# Integrater.net
KiCad netlist of a schematic drawn in Altium Designer
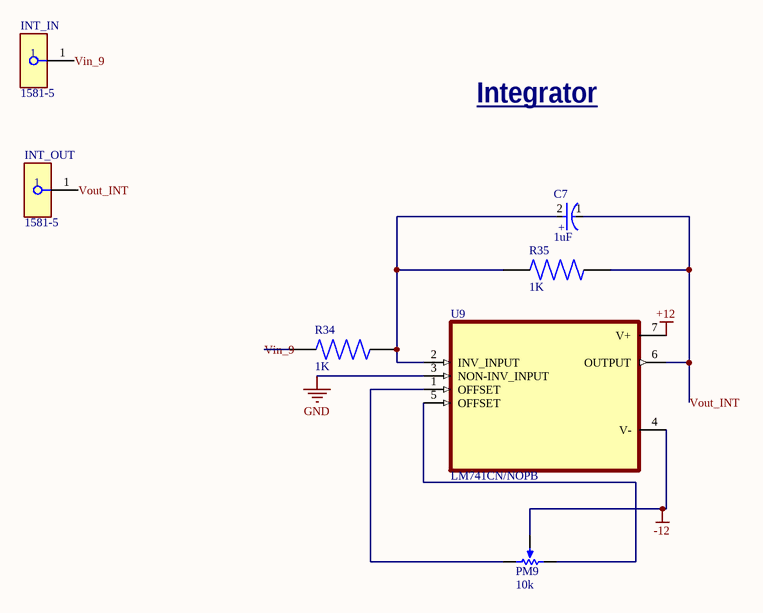
[diagram p0: Integrater.SchDoc]

(export (version "E")
  (design (tool "Eeschema 10.0.6"))
  (components
    (comp (ref "C7")
      (value "1uF")
      (footprint "FP-ECA-2CHG010I-MFG")
      (description "CAP ALUM 1UF 20% 160V RADIAL")
      (fields (field (name "TOLERANCE") "20%"))
      (libsource (lib "Altium Content Vault") (part "a00bbbee19879c290e62620ae7e47b1"))
    )
    (comp (ref "INT_IN")
      (value "1581-5")
      (footprint "FP-1581-5-MFG")
      (description "CONN BANANA JACK TURRET GREEN")
      (libsource (lib "Altium Content Vault") (part "c5c826e0c4b67fe3b42ef77f2d4decc"))
    )
    (comp (ref "INT_OUT")
      (value "1581-5")
      (footprint "FP-1581-5-MFG")
      (description "CONN BANANA JACK TURRET GREEN")
      (libsource (lib "Altium Content Vault") (part "c5c826e0c4b67fe3b42ef77f2d4decc"))
    )
    (comp (ref "PM9")
      (value "10k")
      (footprint "BOUR-3362P")
      (description "Square Trimpot(R) Trimming Potentiometer, 10 KOhm, 300 V, -55 to 125 degC, 3-Pin THD, RoHS, Tube")
      (fields (field (name "TOLERANCE") "1%"))
      (libsource (lib "Altium Content Vault") (part "RES-POT-3"))
    )
    (comp (ref "R34")
      (value "1K")
      (footprint "RESAD1100W55L680D260")
      (description "1.07 kOhms Â±1% 0.25W, 1/4W Through Hole Resistor Axial - Metal Film")
      (fields (field (name "MF") "Yageo") (field (name "MP") "MFR-25FBF52-1K"))
      (libsource (lib "MFR-25FBF52-1K") (part "MFR-25FBF52-1K"))
    )
    (comp (ref "R35")
      (value "1K")
      (footprint "RESAD1100W55L680D260")
      (description "1.07 kOhms Â±1% 0.25W, 1/4W Through Hole Resistor Axial - Metal Film")
      (fields (field (name "MF") "Yageo") (field (name "MP") "MFR-25FBF52-1K"))
      (libsource (lib "MFR-25FBF52-1K") (part "MFR-25FBF52-1K"))
    )
    (comp (ref "U9")
      (value "LM741CN/NOPB")
      (footprint "DIP794W45P254L959H508Q8")
      (description "Single, 44-V, 1-MHz operational amplifier")
      (fields (field (name "MF") "Texas Instruments"))
      (libsource (lib "LM741CN_NOPB (1)") (part "LM741CN/NOPB"))
    )
  )
  (nets
    (net (code "1") (name "+12") (class "Default")
      (node (ref "U9") (pin "7") (pinfunction "V+_7") (pintype "power_in"))
    )
    (net (code "2") (name "-12") (class "Default")
      (node (ref "PM9") (pin "2") (pinfunction "S_2") (pintype "passive"))
      (node (ref "U9") (pin "4") (pinfunction "V-_4") (pintype "power_in"))
    )
    (net (code "3") (name "/Vin_9") (class "Default")
      (node (ref "INT_IN") (pin "1") (pinfunction "1_1") (pintype "passive"))
      (node (ref "R34") (pin "1") (pinfunction "1_1") (pintype "passive"))
    )
    (net (code "4") (name "/Vout_INT") (class "Default")
      (node (ref "C7") (pin "1") (pinfunction "C_1") (pintype "passive"))
      (node (ref "INT_OUT") (pin "1") (pinfunction "1_1") (pintype "passive"))
      (node (ref "R35") (pin "2") (pinfunction "2_2") (pintype "passive"))
      (node (ref "U9") (pin "6") (pinfunction "OUTPUT_6") (pintype "output"))
    )
    (net (code "5") (name "GND") (class "Default")
      (node (ref "U9") (pin "3") (pinfunction "NON-INV_INPUT_3") (pintype "input"))
    )
    (net (code "6") (name "Net-(C7-A)") (class "Default")
      (node (ref "C7") (pin "2") (pinfunction "A_2") (pintype "passive"))
      (node (ref "R34") (pin "2") (pinfunction "2_2") (pintype "passive"))
      (node (ref "R35") (pin "1") (pinfunction "1_1") (pintype "passive"))
      (node (ref "U9") (pin "2") (pinfunction "INV_INPUT_2") (pintype "input"))
    )
    (net (code "7") (name "Net-(PM9-CCW)") (class "Default")
      (node (ref "PM9") (pin "1") (pinfunction "CCW_1") (pintype "passive"))
      (node (ref "U9") (pin "5") (pinfunction "OFFSET_5") (pintype "input"))
    )
    (net (code "8") (name "Net-(PM9-CW)") (class "Default")
      (node (ref "PM9") (pin "3") (pinfunction "CW_3") (pintype "passive"))
      (node (ref "U9") (pin "1") (pinfunction "OFFSET_1") (pintype "input"))
    )
  )
)
